# Active_Probe_Proto2.net
KiCad netlist of a schematic drawn in EAGLE
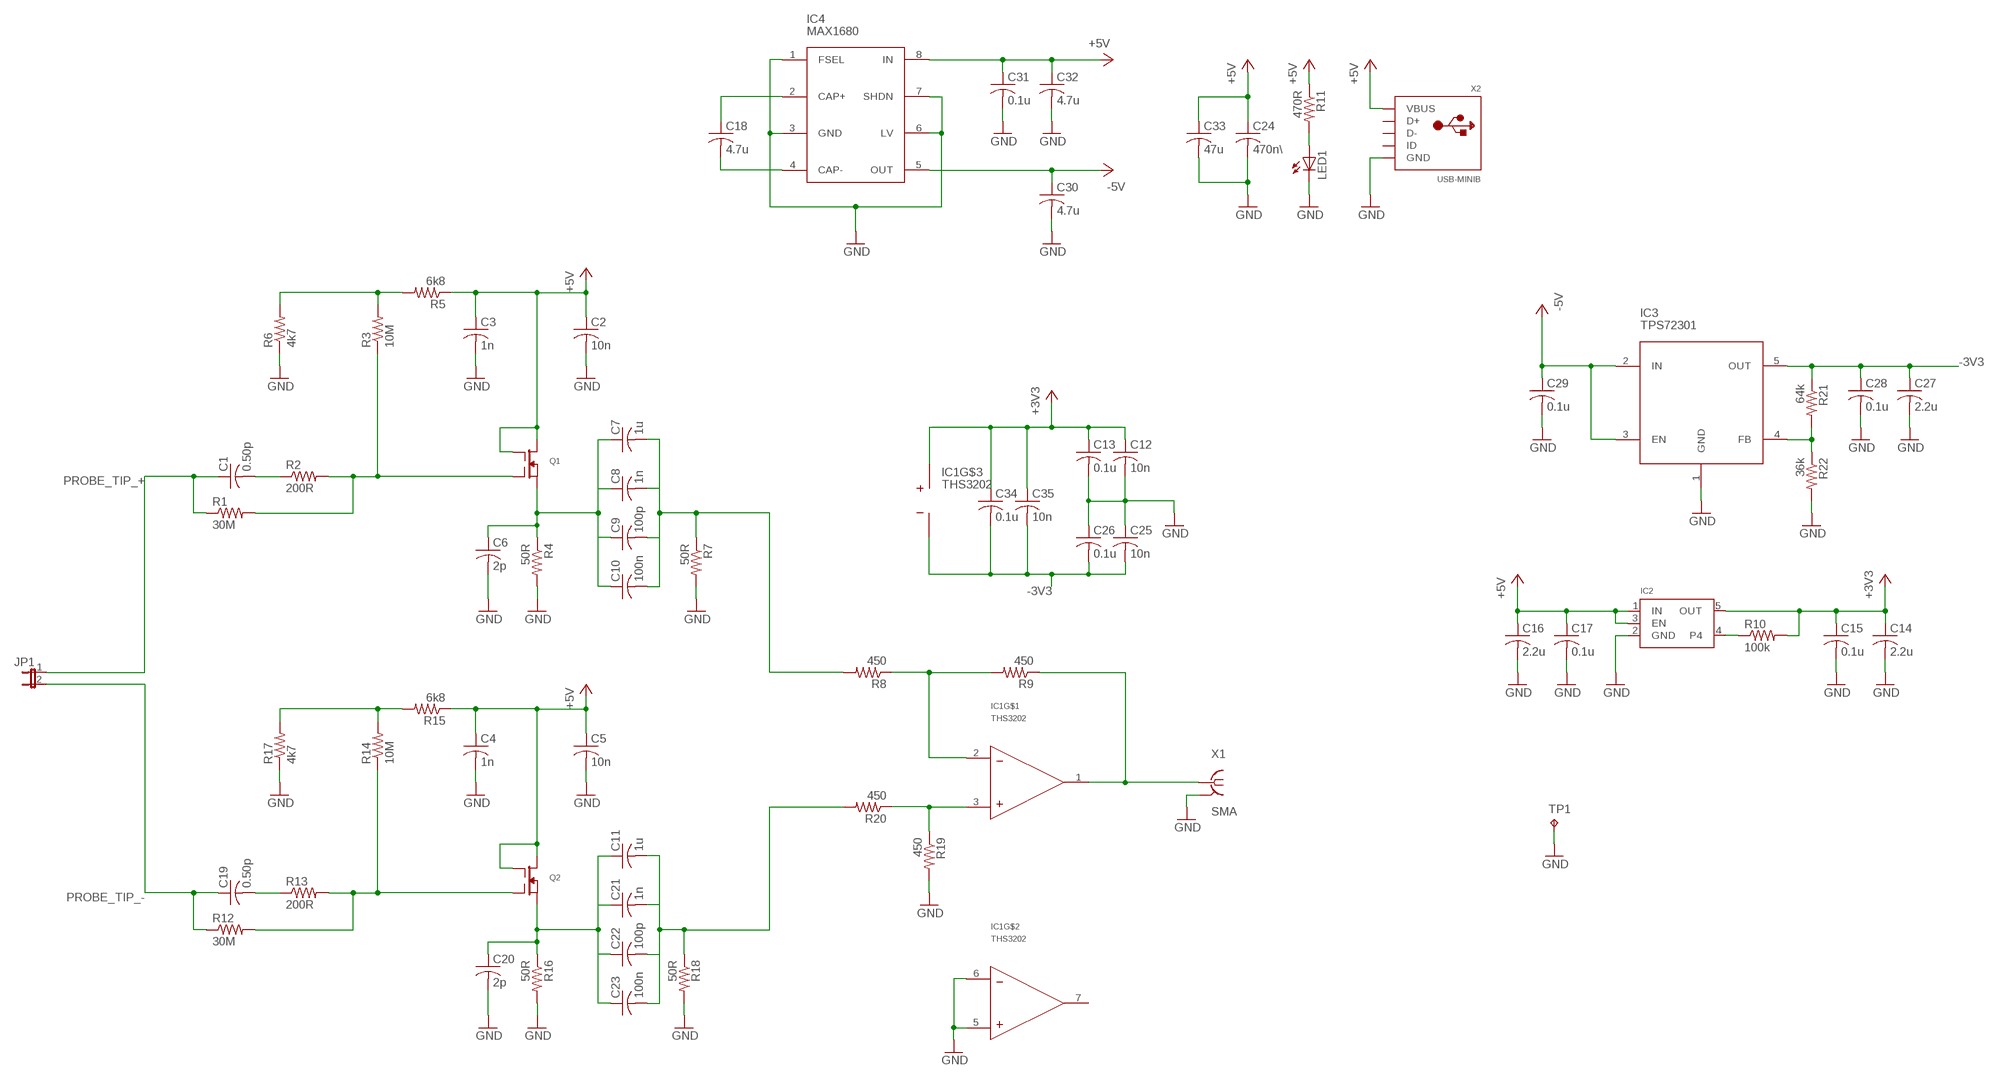
[diagram p0: schematic, sheet 1]

(export (version "E")
  (design (tool "Eeschema 10.0.6"))
  (components
    (comp (ref "C1")
      (value "0.50p")
      (footprint "eagle-import:C0603")
      (libsource (lib "eagle-import") (part "C-USC0603"))
    )
    (comp (ref "C2")
      (value "10n")
      (footprint "eagle-import:C0603")
      (libsource (lib "eagle-import") (part "C-USC0603"))
    )
    (comp (ref "C3")
      (value "1n")
      (footprint "eagle-import:C0603")
      (libsource (lib "eagle-import") (part "C-USC0603"))
    )
    (comp (ref "C4")
      (value "1n")
      (footprint "eagle-import:C0603")
      (libsource (lib "eagle-import") (part "C-USC0603"))
    )
    (comp (ref "C5")
      (value "10n")
      (footprint "eagle-import:C0603")
      (libsource (lib "eagle-import") (part "C-USC0603"))
    )
    (comp (ref "C6")
      (value "2p")
      (footprint "eagle-import:C0603")
      (libsource (lib "eagle-import") (part "C-USC0603"))
    )
    (comp (ref "C7")
      (value "1u")
      (footprint "eagle-import:C0603")
      (libsource (lib "eagle-import") (part "C-USC0603"))
    )
    (comp (ref "C8")
      (value "1n")
      (footprint "eagle-import:C0603")
      (libsource (lib "eagle-import") (part "C-USC0603"))
    )
    (comp (ref "C9")
      (value "100p")
      (footprint "eagle-import:C0603")
      (libsource (lib "eagle-import") (part "C-USC0603"))
    )
    (comp (ref "C10")
      (value "100n")
      (footprint "eagle-import:C0603")
      (libsource (lib "eagle-import") (part "C-USC0603"))
    )
    (comp (ref "C11")
      (value "1u")
      (footprint "eagle-import:C0603")
      (libsource (lib "eagle-import") (part "C-USC0603"))
    )
    (comp (ref "C12")
      (value "10n")
      (footprint "eagle-import:C0603")
      (libsource (lib "eagle-import") (part "C-USC0603"))
    )
    (comp (ref "C13")
      (value "0.1u")
      (footprint "eagle-import:C0603")
      (libsource (lib "eagle-import") (part "C-USC0603"))
    )
    (comp (ref "C14")
      (value "2.2u")
      (footprint "eagle-import:C0603")
      (libsource (lib "eagle-import") (part "C-USC0603"))
    )
    (comp (ref "C15")
      (value "0.1u")
      (footprint "eagle-import:C0603")
      (libsource (lib "eagle-import") (part "C-USC0603"))
    )
    (comp (ref "C16")
      (value "2.2u")
      (footprint "eagle-import:C0603")
      (libsource (lib "eagle-import") (part "C-USC0603"))
    )
    (comp (ref "C17")
      (value "0.1u")
      (footprint "eagle-import:C0603")
      (libsource (lib "eagle-import") (part "C-USC0603"))
    )
    (comp (ref "C18")
      (value "4.7u")
      (footprint "eagle-import:C0603")
      (libsource (lib "eagle-import") (part "C-USC0603"))
    )
    (comp (ref "C19")
      (value "0.50p")
      (footprint "eagle-import:C0603")
      (libsource (lib "eagle-import") (part "C-USC0603"))
    )
    (comp (ref "C20")
      (value "2p")
      (footprint "eagle-import:C0603")
      (libsource (lib "eagle-import") (part "C-USC0603"))
    )
    (comp (ref "C21")
      (value "1n")
      (footprint "eagle-import:C0603")
      (libsource (lib "eagle-import") (part "C-USC0603"))
    )
    (comp (ref "C22")
      (value "100p")
      (footprint "eagle-import:C0603")
      (libsource (lib "eagle-import") (part "C-USC0603"))
    )
    (comp (ref "C23")
      (value "100n")
      (footprint "eagle-import:C0603")
      (libsource (lib "eagle-import") (part "C-USC0603"))
    )
    (comp (ref "C24")
      (value "470n\\")
      (footprint "eagle-import:C0603")
      (libsource (lib "eagle-import") (part "C-USC0603"))
    )
    (comp (ref "C25")
      (value "10n")
      (footprint "eagle-import:C0603")
      (libsource (lib "eagle-import") (part "C-USC0603"))
    )
    (comp (ref "C26")
      (value "0.1u")
      (footprint "eagle-import:C0603")
      (libsource (lib "eagle-import") (part "C-USC0603"))
    )
    (comp (ref "C27")
      (value "2.2u")
      (footprint "eagle-import:C0603")
      (libsource (lib "eagle-import") (part "C-USC0603"))
    )
    (comp (ref "C28")
      (value "0.1u")
      (footprint "eagle-import:C0603")
      (libsource (lib "eagle-import") (part "C-USC0603"))
    )
    (comp (ref "C29")
      (value "0.1u")
      (footprint "eagle-import:C0603")
      (libsource (lib "eagle-import") (part "C-USC0603"))
    )
    (comp (ref "C30")
      (value "4.7u")
      (footprint "eagle-import:C0603")
      (libsource (lib "eagle-import") (part "C-USC0603"))
    )
    (comp (ref "C31")
      (value "0.1u")
      (footprint "eagle-import:C0603")
      (libsource (lib "eagle-import") (part "C-USC0603"))
    )
    (comp (ref "C32")
      (value "4.7u")
      (footprint "eagle-import:C0603")
      (libsource (lib "eagle-import") (part "C-USC0603"))
    )
    (comp (ref "C33")
      (value "47u")
      (footprint "eagle-import:C1206")
      (libsource (lib "eagle-import") (part "C-USC1206"))
    )
    (comp (ref "C34")
      (value "0.1u")
      (footprint "eagle-import:C0603")
      (libsource (lib "eagle-import") (part "C-USC0603"))
    )
    (comp (ref "C35")
      (value "10n")
      (footprint "eagle-import:C0603")
      (libsource (lib "eagle-import") (part "C-USC0603"))
    )
    (comp (ref "IC1")
      (value "THS3202")
      (footprint "eagle-import:SOIC8")
      (libsource (lib "eagle-import") (part "THS3202"))
    )
    (comp (ref "IC2")
      (value "VREG_SOT23-5")
      (footprint "eagle-import:SOT23-5")
      (libsource (lib "eagle-import") (part "VREG_SOT23-5"))
    )
    (comp (ref "IC3")
      (value "TPS72301")
      (footprint "eagle-import:SOT23-5L")
      (libsource (lib "eagle-import") (part "TPS72301"))
    )
    (comp (ref "IC4")
      (value "MAX1680")
      (footprint "eagle-import:SO8")
      (libsource (lib "eagle-import") (part "MAX1680/1"))
    )
    (comp (ref "JP1")
      (value "HEADER_SIDE_2POS")
      (footprint "eagle-import:HEADER_SIDE_2POS")
      (libsource (lib "eagle-import") (part "HEADER_SIDE_2POS"))
    )
    (comp (ref "LED1")
      (value "LED3MM")
      (footprint "eagle-import:LED3MM")
      (libsource (lib "eagle-import") (part "LED3MM"))
    )
    (comp (ref "Q1")
      (value "BF998")
      (footprint "eagle-import:SOT143B")
      (libsource (lib "eagle-import") (part "BF998"))
    )
    (comp (ref "Q2")
      (value "BF998")
      (footprint "eagle-import:SOT143B")
      (libsource (lib "eagle-import") (part "BF998"))
    )
    (comp (ref "R1")
      (value "30M")
      (footprint "eagle-import:R0603")
      (libsource (lib "eagle-import") (part "R-US_R0603"))
    )
    (comp (ref "R2")
      (value "200R")
      (footprint "eagle-import:R0603")
      (libsource (lib "eagle-import") (part "R-US_R0603"))
    )
    (comp (ref "R3")
      (value "10M")
      (footprint "eagle-import:R0603")
      (libsource (lib "eagle-import") (part "R-US_R0603"))
    )
    (comp (ref "R4")
      (value "50R")
      (footprint "eagle-import:R0603")
      (libsource (lib "eagle-import") (part "R-US_R0603"))
    )
    (comp (ref "R5")
      (value "6k8")
      (footprint "eagle-import:R0603")
      (libsource (lib "eagle-import") (part "R-US_R0603"))
    )
    (comp (ref "R6")
      (value "4k7")
      (footprint "eagle-import:R0603")
      (libsource (lib "eagle-import") (part "R-US_R0603"))
    )
    (comp (ref "R7")
      (value "50R")
      (footprint "eagle-import:R0603")
      (libsource (lib "eagle-import") (part "R-US_R0603"))
    )
    (comp (ref "R8")
      (value "450")
      (footprint "eagle-import:R0603")
      (libsource (lib "eagle-import") (part "R-US_R0603"))
    )
    (comp (ref "R9")
      (value "450")
      (footprint "eagle-import:R0603")
      (libsource (lib "eagle-import") (part "R-US_R0603"))
    )
    (comp (ref "R10")
      (value "100k")
      (footprint "eagle-import:R0603")
      (libsource (lib "eagle-import") (part "R-US_R0603"))
    )
    (comp (ref "R11")
      (value "470R")
      (footprint "eagle-import:R0805")
      (libsource (lib "eagle-import") (part "R-US_R0805"))
    )
    (comp (ref "R12")
      (value "30M")
      (footprint "eagle-import:R0603")
      (libsource (lib "eagle-import") (part "R-US_R0603"))
    )
    (comp (ref "R13")
      (value "200R")
      (footprint "eagle-import:R0603")
      (libsource (lib "eagle-import") (part "R-US_R0603"))
    )
    (comp (ref "R14")
      (value "10M")
      (footprint "eagle-import:R0603")
      (libsource (lib "eagle-import") (part "R-US_R0603"))
    )
    (comp (ref "R15")
      (value "6k8")
      (footprint "eagle-import:R0603")
      (libsource (lib "eagle-import") (part "R-US_R0603"))
    )
    (comp (ref "R16")
      (value "50R")
      (footprint "eagle-import:R0603")
      (libsource (lib "eagle-import") (part "R-US_R0603"))
    )
    (comp (ref "R17")
      (value "4k7")
      (footprint "eagle-import:R0603")
      (libsource (lib "eagle-import") (part "R-US_R0603"))
    )
    (comp (ref "R18")
      (value "50R")
      (footprint "eagle-import:R0603")
      (libsource (lib "eagle-import") (part "R-US_R0603"))
    )
    (comp (ref "R19")
      (value "450")
      (footprint "eagle-import:R0603")
      (libsource (lib "eagle-import") (part "R-US_R0603"))
    )
    (comp (ref "R20")
      (value "450")
      (footprint "eagle-import:R0603")
      (libsource (lib "eagle-import") (part "R-US_R0603"))
    )
    (comp (ref "R21")
      (value "64k")
      (footprint "eagle-import:R0603")
      (libsource (lib "eagle-import") (part "R-US_R0603"))
    )
    (comp (ref "R22")
      (value "36k")
      (footprint "eagle-import:R0603")
      (libsource (lib "eagle-import") (part "R-US_R0603"))
    )
    (comp (ref "TP1")
      (value "TPTP20SQ")
      (footprint "eagle-import:TP20SQ")
      (libsource (lib "eagle-import") (part "TPTP20SQ"))
    )
    (comp (ref "X1")
      (value "SMA")
      (footprint "eagle-import:J502-ND-142-0701-801_806")
      (fields (field (name "MF") "JOHNSON COMPONENTS") (field (name "MPN") "142-0701-801"))
      (libsource (lib "eagle-import") (part "SMA-142-0701-801/806"))
    )
    (comp (ref "X2")
      (value "USB-MINIB")
      (footprint "eagle-import:USB-MINIB")
      (libsource (lib "eagle-import") (part "USBMINIB"))
    )
  )
  (nets
    (net (code "1") (name "+3V3") (class "Default")
      (node (ref "C12") (pin "1") (pinfunction "1_1") (pintype "passive"))
      (node (ref "C13") (pin "1") (pinfunction "1_1") (pintype "passive"))
      (node (ref "C14") (pin "1") (pinfunction "1_1") (pintype "passive"))
      (node (ref "C15") (pin "1") (pinfunction "1_1") (pintype "passive"))
      (node (ref "C34") (pin "1") (pinfunction "1_1") (pintype "passive"))
      (node (ref "C35") (pin "1") (pinfunction "1_1") (pintype "passive"))
      (node (ref "IC1") (pin "8") (pinfunction "VCC_8") (pintype "power_in"))
      (node (ref "IC2") (pin "5") (pinfunction "OUT_5") (pintype "bidirectional"))
      (node (ref "R10") (pin "2") (pinfunction "2_2") (pintype "passive"))
    )
    (net (code "2") (name "+5V") (class "Default")
      (node (ref "C16") (pin "1") (pinfunction "1_1") (pintype "passive"))
      (node (ref "C17") (pin "1") (pinfunction "1_1") (pintype "passive"))
      (node (ref "C2") (pin "1") (pinfunction "1_1") (pintype "passive"))
      (node (ref "C24") (pin "1") (pinfunction "1_1") (pintype "passive"))
      (node (ref "C3") (pin "1") (pinfunction "1_1") (pintype "passive"))
      (node (ref "C31") (pin "1") (pinfunction "1_1") (pintype "passive"))
      (node (ref "C32") (pin "1") (pinfunction "1_1") (pintype "passive"))
      (node (ref "C33") (pin "1") (pinfunction "1_1") (pintype "passive"))
      (node (ref "C4") (pin "1") (pinfunction "1_1") (pintype "passive"))
      (node (ref "C5") (pin "1") (pinfunction "1_1") (pintype "passive"))
      (node (ref "IC2") (pin "1") (pinfunction "IN_1") (pintype "bidirectional"))
      (node (ref "IC2") (pin "3") (pinfunction "EN_3") (pintype "bidirectional"))
      (node (ref "IC4") (pin "8") (pinfunction "IN_8") (pintype "bidirectional"))
      (node (ref "Q1") (pin "2") (pinfunction "D_2") (pintype "bidirectional"))
      (node (ref "Q1") (pin "3") (pinfunction "G2_3") (pintype "bidirectional"))
      (node (ref "Q2") (pin "2") (pinfunction "D_2") (pintype "bidirectional"))
      (node (ref "Q2") (pin "3") (pinfunction "G2_3") (pintype "bidirectional"))
      (node (ref "R11") (pin "1") (pinfunction "1_1") (pintype "passive"))
      (node (ref "R15") (pin "1") (pinfunction "1_1") (pintype "passive"))
      (node (ref "R5") (pin "1") (pinfunction "1_1") (pintype "passive"))
      (node (ref "X2") (pin "VBUS") (pinfunction "VBUS_VBUS") (pintype "power_in"))
    )
    (net (code "3") (name "-5V") (class "Default")
      (node (ref "C29") (pin "1") (pinfunction "1_1") (pintype "passive"))
      (node (ref "C30") (pin "1") (pinfunction "1_1") (pintype "passive"))
      (node (ref "IC3") (pin "2") (pinfunction "IN_2") (pintype "bidirectional"))
      (node (ref "IC3") (pin "3") (pinfunction "EN_3") (pintype "bidirectional"))
      (node (ref "IC4") (pin "5") (pinfunction "OUT_5") (pintype "bidirectional"))
    )
    (net (code "4") (name "/-3V3") (class "Default")
      (node (ref "C25") (pin "2") (pinfunction "2_2") (pintype "passive"))
      (node (ref "C26") (pin "2") (pinfunction "2_2") (pintype "passive"))
      (node (ref "C27") (pin "1") (pinfunction "1_1") (pintype "passive"))
      (node (ref "C28") (pin "1") (pinfunction "1_1") (pintype "passive"))
      (node (ref "C34") (pin "2") (pinfunction "2_2") (pintype "passive"))
      (node (ref "C35") (pin "2") (pinfunction "2_2") (pintype "passive"))
      (node (ref "IC1") (pin "4") (pinfunction "GND_4") (pintype "power_in"))
      (node (ref "IC3") (pin "5") (pinfunction "OUT_5") (pintype "bidirectional"))
      (node (ref "R21") (pin "1") (pinfunction "1_1") (pintype "passive"))
    )
    (net (code "5") (name "/PROBE_TIP_+") (class "Default")
      (node (ref "C1") (pin "1") (pinfunction "1_1") (pintype "passive"))
      (node (ref "JP1") (pin "1") (pinfunction "1_1") (pintype "passive"))
      (node (ref "R1") (pin "1") (pinfunction "1_1") (pintype "passive"))
    )
    (net (code "6") (name "/PROBE_TIP_-") (class "Default")
      (node (ref "C19") (pin "1") (pinfunction "1_1") (pintype "passive"))
      (node (ref "JP1") (pin "2") (pinfunction "2_2") (pintype "passive"))
      (node (ref "R12") (pin "1") (pinfunction "1_1") (pintype "passive"))
    )
    (net (code "7") (name "GND") (class "Default")
      (node (ref "C12") (pin "2") (pinfunction "2_2") (pintype "passive"))
      (node (ref "C13") (pin "2") (pinfunction "2_2") (pintype "passive"))
      (node (ref "C14") (pin "2") (pinfunction "2_2") (pintype "passive"))
      (node (ref "C15") (pin "2") (pinfunction "2_2") (pintype "passive"))
      (node (ref "C16") (pin "2") (pinfunction "2_2") (pintype "passive"))
      (node (ref "C17") (pin "2") (pinfunction "2_2") (pintype "passive"))
      (node (ref "C2") (pin "2") (pinfunction "2_2") (pintype "passive"))
      (node (ref "C20") (pin "2") (pinfunction "2_2") (pintype "passive"))
      (node (ref "C24") (pin "2") (pinfunction "2_2") (pintype "passive"))
      (node (ref "C25") (pin "1") (pinfunction "1_1") (pintype "passive"))
      (node (ref "C26") (pin "1") (pinfunction "1_1") (pintype "passive"))
      (node (ref "C27") (pin "2") (pinfunction "2_2") (pintype "passive"))
      (node (ref "C28") (pin "2") (pinfunction "2_2") (pintype "passive"))
      (node (ref "C29") (pin "2") (pinfunction "2_2") (pintype "passive"))
      (node (ref "C3") (pin "2") (pinfunction "2_2") (pintype "passive"))
      (node (ref "C30") (pin "2") (pinfunction "2_2") (pintype "passive"))
      (node (ref "C31") (pin "2") (pinfunction "2_2") (pintype "passive"))
      (node (ref "C32") (pin "2") (pinfunction "2_2") (pintype "passive"))
      (node (ref "C33") (pin "2") (pinfunction "2_2") (pintype "passive"))
      (node (ref "C4") (pin "2") (pinfunction "2_2") (pintype "passive"))
      (node (ref "C5") (pin "2") (pinfunction "2_2") (pintype "passive"))
      (node (ref "C6") (pin "2") (pinfunction "2_2") (pintype "passive"))
      (node (ref "IC1") (pin "5") (pinfunction "IN+_5") (pintype "input"))
      (node (ref "IC1") (pin "6") (pinfunction "IN-_6") (pintype "input"))
      (node (ref "IC2") (pin "2") (pinfunction "GND_2") (pintype "bidirectional"))
      (node (ref "IC3") (pin "1") (pinfunction "GND_1") (pintype "bidirectional"))
      (node (ref "IC4") (pin "1") (pinfunction "FSEL_1") (pintype "bidirectional"))
      (node (ref "IC4") (pin "3") (pinfunction "GND_3") (pintype "bidirectional"))
      (node (ref "IC4") (pin "6") (pinfunction "LV_6") (pintype "bidirectional"))
      (node (ref "IC4") (pin "7") (pinfunction "SHDN_7") (pintype "bidirectional"))
      (node (ref "LED1") (pin "K") (pinfunction "C_K") (pintype "passive"))
      (node (ref "R16") (pin "2") (pinfunction "2_2") (pintype "passive"))
      (node (ref "R17") (pin "1") (pinfunction "1_1") (pintype "passive"))
      (node (ref "R18") (pin "2") (pinfunction "2_2") (pintype "passive"))
      (node (ref "R19") (pin "2") (pinfunction "2_2") (pintype "passive"))
      (node (ref "R22") (pin "2") (pinfunction "2_2") (pintype "passive"))
      (node (ref "R4") (pin "2") (pinfunction "2_2") (pintype "passive"))
      (node (ref "R6") (pin "1") (pinfunction "1_1") (pintype "passive"))
      (node (ref "R7") (pin "2") (pinfunction "2_2") (pintype "passive"))
      (node (ref "TP1") (pin "TP") (pinfunction "TP_TP") (pintype "input"))
      (node (ref "X1") (pin "G@1") (pinfunction "GND_G@1") (pintype "power_in"))
      (node (ref "X2") (pin "GND") (pinfunction "GND_GND") (pintype "power_in"))
    )
    (net (code "8") (name "Net-(C1-Pad2)") (class "Default")
      (node (ref "C1") (pin "2") (pinfunction "2_2") (pintype "passive"))
      (node (ref "R2") (pin "1") (pinfunction "1_1") (pintype "passive"))
    )
    (net (code "9") (name "Net-(C10-Pad2)") (class "Default")
      (node (ref "C10") (pin "2") (pinfunction "2_2") (pintype "passive"))
      (node (ref "C7") (pin "2") (pinfunction "2_2") (pintype "passive"))
      (node (ref "C8") (pin "2") (pinfunction "2_2") (pintype "passive"))
      (node (ref "C9") (pin "2") (pinfunction "2_2") (pintype "passive"))
      (node (ref "R7") (pin "1") (pinfunction "1_1") (pintype "passive"))
      (node (ref "R8") (pin "2") (pinfunction "2_2") (pintype "passive"))
    )
    (net (code "10") (name "Net-(C11-Pad2)") (class "Default")
      (node (ref "C11") (pin "2") (pinfunction "2_2") (pintype "passive"))
      (node (ref "C21") (pin "2") (pinfunction "2_2") (pintype "passive"))
      (node (ref "C22") (pin "2") (pinfunction "2_2") (pintype "passive"))
      (node (ref "C23") (pin "2") (pinfunction "2_2") (pintype "passive"))
      (node (ref "R18") (pin "1") (pinfunction "1_1") (pintype "passive"))
      (node (ref "R20") (pin "2") (pinfunction "2_2") (pintype "passive"))
    )
    (net (code "11") (name "Net-(C19-Pad2)") (class "Default")
      (node (ref "C19") (pin "2") (pinfunction "2_2") (pintype "passive"))
      (node (ref "R13") (pin "1") (pinfunction "1_1") (pintype "passive"))
    )
    (net (code "12") (name "Net-(IC1A-IN+)") (class "Default")
      (node (ref "IC1") (pin "3") (pinfunction "IN+_3") (pintype "input"))
      (node (ref "R19") (pin "1") (pinfunction "1_1") (pintype "passive"))
      (node (ref "R20") (pin "1") (pinfunction "1_1") (pintype "passive"))
    )
    (net (code "13") (name "Net-(IC1A-IN-)") (class "Default")
      (node (ref "IC1") (pin "2") (pinfunction "IN-_2") (pintype "input"))
      (node (ref "R8") (pin "1") (pinfunction "1_1") (pintype "passive"))
      (node (ref "R9") (pin "2") (pinfunction "2_2") (pintype "passive"))
    )
    (net (code "14") (name "Net-(IC1A-OUT)") (class "Default")
      (node (ref "IC1") (pin "1") (pinfunction "OUT_1") (pintype "output"))
      (node (ref "R9") (pin "1") (pinfunction "1_1") (pintype "passive"))
      (node (ref "X1") (pin "1") (pinfunction "1_1") (pintype "passive"))
    )
    (net (code "15") (name "Net-(IC2-P4)") (class "Default")
      (node (ref "IC2") (pin "4") (pinfunction "P4_4") (pintype "bidirectional"))
      (node (ref "R10") (pin "1") (pinfunction "1_1") (pintype "passive"))
    )
    (net (code "16") (name "Net-(IC3-FB)") (class "Default")
      (node (ref "IC3") (pin "4") (pinfunction "FB_4") (pintype "bidirectional"))
      (node (ref "R21") (pin "2") (pinfunction "2_2") (pintype "passive"))
      (node (ref "R22") (pin "1") (pinfunction "1_1") (pintype "passive"))
    )
    (net (code "17") (name "Net-(IC4-CAP+)") (class "Default")
      (node (ref "C18") (pin "1") (pinfunction "1_1") (pintype "passive"))
      (node (ref "IC4") (pin "2") (pinfunction "CAP+_2") (pintype "bidirectional"))
    )
    (net (code "18") (name "Net-(IC4-CAP-)") (class "Default")
      (node (ref "C18") (pin "2") (pinfunction "2_2") (pintype "passive"))
      (node (ref "IC4") (pin "4") (pinfunction "CAP-_4") (pintype "bidirectional"))
    )
    (net (code "19") (name "Net-(LED1-PadA)") (class "Default")
      (node (ref "LED1") (pin "A") (pinfunction "A_A") (pintype "passive"))
      (node (ref "R11") (pin "2") (pinfunction "2_2") (pintype "passive"))
    )
    (net (code "20") (name "Net-(Q1-G1)") (class "Default")
      (node (ref "Q1") (pin "4") (pinfunction "G1_4") (pintype "bidirectional"))
      (node (ref "R1") (pin "2") (pinfunction "2_2") (pintype "passive"))
      (node (ref "R2") (pin "2") (pinfunction "2_2") (pintype "passive"))
      (node (ref "R3") (pin "1") (pinfunction "1_1") (pintype "passive"))
    )
    (net (code "21") (name "Net-(Q1-S)") (class "Default")
      (node (ref "C10") (pin "1") (pinfunction "1_1") (pintype "passive"))
      (node (ref "C6") (pin "1") (pinfunction "1_1") (pintype "passive"))
      (node (ref "C7") (pin "1") (pinfunction "1_1") (pintype "passive"))
      (node (ref "C8") (pin "1") (pinfunction "1_1") (pintype "passive"))
      (node (ref "C9") (pin "1") (pinfunction "1_1") (pintype "passive"))
      (node (ref "Q1") (pin "1") (pinfunction "S_1") (pintype "bidirectional"))
      (node (ref "R4") (pin "1") (pinfunction "1_1") (pintype "passive"))
    )
    (net (code "22") (name "Net-(Q2-G1)") (class "Default")
      (node (ref "Q2") (pin "4") (pinfunction "G1_4") (pintype "bidirectional"))
      (node (ref "R12") (pin "2") (pinfunction "2_2") (pintype "passive"))
      (node (ref "R13") (pin "2") (pinfunction "2_2") (pintype "passive"))
      (node (ref "R14") (pin "1") (pinfunction "1_1") (pintype "passive"))
    )
    (net (code "23") (name "Net-(Q2-S)") (class "Default")
      (node (ref "C11") (pin "1") (pinfunction "1_1") (pintype "passive"))
      (node (ref "C20") (pin "1") (pinfunction "1_1") (pintype "passive"))
      (node (ref "C21") (pin "1") (pinfunction "1_1") (pintype "passive"))
      (node (ref "C22") (pin "1") (pinfunction "1_1") (pintype "passive"))
      (node (ref "C23") (pin "1") (pinfunction "1_1") (pintype "passive"))
      (node (ref "Q2") (pin "1") (pinfunction "S_1") (pintype "bidirectional"))
      (node (ref "R16") (pin "1") (pinfunction "1_1") (pintype "passive"))
    )
    (net (code "24") (name "Net-(R3-Pad2)") (class "Default")
      (node (ref "R3") (pin "2") (pinfunction "2_2") (pintype "passive"))
      (node (ref "R5") (pin "2") (pinfunction "2_2") (pintype "passive"))
      (node (ref "R6") (pin "2") (pinfunction "2_2") (pintype "passive"))
    )
    (net (code "25") (name "Net-(R14-Pad2)") (class "Default")
      (node (ref "R14") (pin "2") (pinfunction "2_2") (pintype "passive"))
      (node (ref "R15") (pin "2") (pinfunction "2_2") (pintype "passive"))
      (node (ref "R17") (pin "2") (pinfunction "2_2") (pintype "passive"))
    )
    (net (code "26") (name "unconnected-(IC1B-OUT-Pad7)") (class "Default")
      (node (ref "IC1") (pin "7") (pinfunction "OUT_7") (pintype "output"))
    )
    (net (code "27") (name "unconnected-(X2-PadD+)") (class "Default")
      (node (ref "X2") (pin "D+") (pinfunction "D+_D+") (pintype "bidirectional"))
    )
    (net (code "28") (name "unconnected-(X2-PadD-)") (class "Default")
      (node (ref "X2") (pin "D-") (pinfunction "D-_D-") (pintype "bidirectional"))
    )
    (net (code "29") (name "unconnected-(X2-PadID)") (class "Default")
      (node (ref "X2") (pin "ID") (pinfunction "ID_ID") (pintype "bidirectional"))
    )
  )
)
